# Project2.net
KiCad netlist of a schematic drawn in Altium Designer
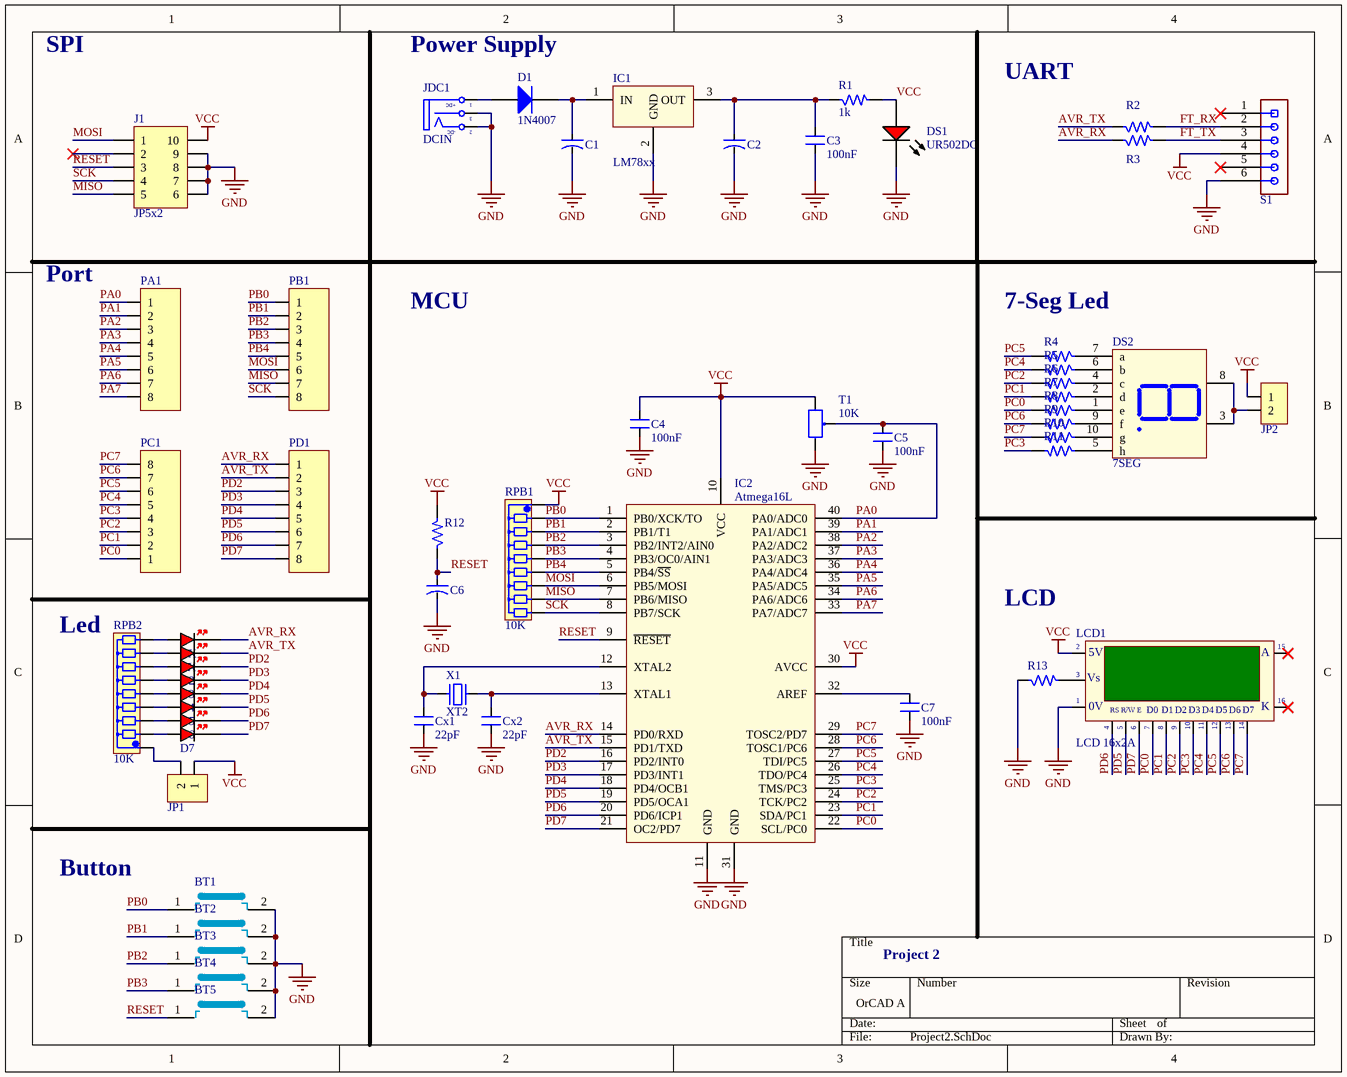
[diagram p0: Project2.SchDoc]

(export (version "E")
  (design (tool "Eeschema 10.0.6"))
  (components
    (comp (ref "BT1") (value "BT") (footprint "SW4") (libsource (lib "My library altium") (part "BUTTON")))
    (comp (ref "BT2") (value "BT") (footprint "SW4") (libsource (lib "My library altium") (part "BUTTON")))
    (comp (ref "BT3") (value "BT") (footprint "SW4") (libsource (lib "My library altium") (part "BUTTON")))
    (comp (ref "BT4") (value "BT") (footprint "SW4") (libsource (lib "My library altium") (part "BUTTON")))
    (comp (ref "BT5") (value "BT") (footprint "SW4") (libsource (lib "My library altium") (part "BUTTON")))
    (comp (ref "C1")
      (value "CN-ALU-DIP")
      (footprint "CA-ALU-8")
      (description "Capacitor (Semiconductor SIM Model)")
      (fields (field (name "PUBLISHER") "Altium Limited"))
      (libsource (lib "Altium Library") (part "CN-ALU-DIP"))
    )
    (comp (ref "C2")
      (value "CN-ALU-DIP")
      (footprint "CA-ALU-8")
      (description "Capacitor (Semiconductor SIM Model)")
      (fields (field (name "PUBLISHER") "Altium Limited"))
      (libsource (lib "Altium Library") (part "CN-ALU-DIP"))
    )
    (comp (ref "C3")
      (value "100nF")
      (footprint "CN1.5")
      (description "Cap np Cremic  682pF => 104 pF")
      (fields (field (name "Comment") "CN1.5") (field (name "SOURCE") "syhaunguyen.SchLib"))
      (libsource (lib "Ha Noi University of Science and Technology") (part "CN1.5"))
    )
    (comp (ref "C4")
      (value "100nF")
      (footprint "CN1.5")
      (description "Cap np Cremic  682pF => 104 pF")
      (fields (field (name "Comment") "CN1.5") (field (name "SOURCE") "syhaunguyen.SchLib"))
      (libsource (lib "Ha Noi University of Science and Technology") (part "CN1.5"))
    )
    (comp (ref "C5")
      (value "100nF")
      (footprint "CN1.5")
      (description "Cap np Cremic  682pF => 104 pF")
      (fields (field (name "Comment") "CN1.5") (field (name "SOURCE") "syhaunguyen.SchLib"))
      (libsource (lib "Ha Noi University of Science and Technology") (part "CN1.5"))
    )
    (comp (ref "C6")
      (value "CN-ALU-DIP")
      (footprint "CA-ALU-5W")
      (description "Capacitor (Semiconductor SIM Model)")
      (fields (field (name "PUBLISHER") "Altium Limited"))
      (libsource (lib "Altium Library") (part "CN-ALU-DIP"))
    )
    (comp (ref "C7")
      (value "100nF")
      (footprint "CN1.5")
      (description "Cap np Cremic  682pF => 104 pF")
      (fields (field (name "Comment") "CN1.5") (field (name "SOURCE") "syhaunguyen.SchLib"))
      (libsource (lib "Ha Noi University of Science and Technology") (part "CN1.5"))
    )
    (comp (ref "Cx1")
      (value "22pF")
      (footprint "CN1")
      (description "Cap np Cremic value 1pF => 100pF")
      (fields (field (name "Comment") "CN0") (field (name "SOURCE") "syhaunguyen.SchLib"))
      (libsource (lib "Ha Noi University of Science and Technology") (part "CN0"))
    )
    (comp (ref "Cx2")
      (value "22pF")
      (footprint "CN1")
      (description "Cap np Cremic value 1pF => 100pF")
      (fields (field (name "Comment") "CN0") (field (name "SOURCE") "syhaunguyen.SchLib"))
      (libsource (lib "Ha Noi University of Science and Technology") (part "CN0"))
    )
    (comp (ref "D1")
      (value "1N4007")
      (footprint "FAIR-DO-41-2")
      (description "General Purpose Rectifier, 1.1 V, 1.0 A, -55 to 175 degC, 2-Pin DO-41, RoHS, Tape and Reel")
      (fields (field (name "MANUFACTURER") "Fairchild"))
      (libsource (lib "Ha Noi University of Science and Technology") (part "KESE-D_K1A2-2"))
    )
    (comp (ref "D2")
      (value "Led Flat")
      (footprint "Led Flat")
      (description "Led Flat 2x5mm")
      (libsource (lib "LedFlat") (part "Led Flat"))
    )
    (comp (ref "D3")
      (value "Led Flat")
      (footprint "Led Flat")
      (description "Led Flat 2x5mm")
      (libsource (lib "LedFlat") (part "Led Flat"))
    )
    (comp (ref "D4")
      (value "Led Flat")
      (footprint "Led Flat")
      (description "Led Flat 2x5mm")
      (libsource (lib "LedFlat") (part "Led Flat"))
    )
    (comp (ref "D5")
      (value "Led Flat")
      (footprint "Led Flat")
      (description "Led Flat 2x5mm")
      (libsource (lib "LedFlat") (part "Led Flat"))
    )
    (comp (ref "D6")
      (value "Led Flat")
      (footprint "Led Flat")
      (description "Led Flat 2x5mm")
      (libsource (lib "LedFlat") (part "Led Flat"))
    )
    (comp (ref "D7")
      (value "Led Flat")
      (footprint "Led Flat")
      (description "Led Flat 2x5mm")
      (libsource (lib "LedFlat") (part "Led Flat"))
    )
    (comp (ref "DS1")
      (value "UR502DC")
      (footprint "CGX-UR502DC")
      (description "Red LED, 80 mW, 30 mA, -25 to 85 degC, 2-Pin THD")
      (fields (field (name "POWER") "80mW") (field (name "MANUFACTURER") "Shenzhen CGX"))
      (libsource (lib "Ha Noi University of Science and Technology") (part "LED-RED-AK-2"))
    )
    (comp (ref "DS2")
      (value "7SEG")
      (footprint "LED7SEG-1-0.56")
      (description "14.2 mm General Purpose Blue 7-Segment Display: CC, RH DP, Gray Surface")
      (fields (field (name "PUBLISHER") "Altium Limited"))
      (libsource (lib "Altium Library") (part "LED7SEG-1"))
    )
    (comp (ref "IC1")
      (value "LM78xx")
      (footprint "QTO-220H3")
      (description "Low-Power Dual Operational Amplifier")
      (fields (field (name "SOURCE") "syhaunguyen.SchLib"))
      (libsource (lib "Ha Noi University of Science and Technology") (part "LM78xx"))
    )
    (comp (ref "IC2")
      (value "Atmega16L")
      (footprint "DIP40PIN")
      (description "8-Bit AVR Microcontroller with 16K Bytes of In-System Programmable Flash Memory")
      (fields (field (name "SOURCE") "syhaunguyen.SchLib"))
      (libsource (lib "Ha Noi University of Science and Technology") (part "Atmega16L"))
    )
    (comp (ref "J1")
      (value "JP5x2")
      (footprint "JP5-D2T")
      (description "WR-PHD 2.54 mm Dual Socket Header")
      (fields
        (field (name "MANUFACTURER") "Würth Elektronik eiSos GmbH")
        (field (name "PARTNO") "61301021821")
        (field (name "CREATED BY") "Karrer Zheng")
      )
      (libsource (lib "Altium Library") (part "JP5x2"))
    )
    (comp (ref "JDC1")
      (value "DCIN")
      (footprint "DC-IN")
      (description "Jac DC input")
      (fields (field (name "SOURCE") "syhaunguyen.SchLib"))
      (libsource (lib "Ha Noi University of Science and Technology") (part "DCIN"))
    )
    (comp (ref "JP1")
      (value "JP1")
      (footprint "JP2-CLOSED")
      (description "WR-PHD 2.54 mm Angled Socket Header")
      (fields
        (field (name "MANUFACTURER") "Würth Elektronik eiSos GmbH")
        (field (name "PARTNO") "613002143121")
        (field (name "CREATED BY") "Karrer Zheng")
      )
      (libsource (lib "Altium Library") (part "JP2"))
    )
    (comp (ref "JP2")
      (value "JP2")
      (footprint "JP2-CLOSED")
      (description "WR-PHD 2.54 mm Angled Socket Header")
      (fields
        (field (name "MANUFACTURER") "Würth Elektronik eiSos GmbH")
        (field (name "PARTNO") "613002143121")
        (field (name "CREATED BY") "Karrer Zheng")
      )
      (libsource (lib "") (part "JP2_1"))
    )
    (comp (ref "LCD1")
      (value "LCD 16x2A")
      (footprint "LCD16X2N")
      (description "LCD dipslay 16 char, 2 line")
      (libsource (lib "Altium Library") (part "LCD16x2A"))
    )
    (comp (ref "PA1")
      (value "JP 1x8 2.54")
      (footprint "JP 1x8 DT")
      (description "Cắm")
      (libsource (lib "Altium_Lib_by_KhueNguyenCreator") (part "JP 1x8 2.54 Duc Thang"))
    )
    (comp (ref "PB1")
      (value "JP 1x8 2.54")
      (footprint "JP 1x8 DT")
      (description "Cắm")
      (libsource (lib "Altium_Lib_by_KhueNguyenCreator") (part "JP 1x8 2.54 Duc Thang"))
    )
    (comp (ref "PC1")
      (value "JP 1x8 2.54")
      (footprint "JP 1x8 DT")
      (description "Cắm")
      (libsource (lib "") (part "JP 1x8 2.54 Duc Thang_1"))
    )
    (comp (ref "PD1")
      (value "JP 1x8 2.54")
      (footprint "JP 1x8 DT")
      (description "Cắm")
      (libsource (lib "Altium_Lib_by_KhueNguyenCreator") (part "JP 1x8 2.54 Duc Thang"))
    )
    (comp (ref "R1")
      (value "1k")
      (footprint "R1/4W")
      (description "Resistor 1/4W")
      (libsource (lib "Library AL") (part "R"))
    )
    (comp (ref "R2")
      (value "R")
      (footprint "R1/4W")
      (description "Resistor 1/4W")
      (fields (field (name "SOURCE") "heromap.SchLib"))
      (libsource (lib "Ha Noi University of Science and Technology") (part "R"))
    )
    (comp (ref "R3")
      (value "R")
      (footprint "R1/4W")
      (description "Resistor 1/4W")
      (fields (field (name "SOURCE") "heromap.SchLib"))
      (libsource (lib "Ha Noi University of Science and Technology") (part "R"))
    )
    (comp (ref "R4")
      (value "R")
      (footprint "R1/4W")
      (description "Resistor 1/4W")
      (fields (field (name "SOURCE") "heromap.SchLib"))
      (libsource (lib "Ha Noi University of Science and Technology") (part "R"))
    )
    (comp (ref "R5")
      (value "R")
      (footprint "R1/4W")
      (description "Resistor 1/4W")
      (fields (field (name "SOURCE") "heromap.SchLib"))
      (libsource (lib "Ha Noi University of Science and Technology") (part "R"))
    )
    (comp (ref "R6")
      (value "R")
      (footprint "R1/4W")
      (description "Resistor 1/4W")
      (fields (field (name "SOURCE") "heromap.SchLib"))
      (libsource (lib "Ha Noi University of Science and Technology") (part "R"))
    )
    (comp (ref "R7")
      (value "R")
      (footprint "R1/4W")
      (description "Resistor 1/4W")
      (fields (field (name "SOURCE") "heromap.SchLib"))
      (libsource (lib "Ha Noi University of Science and Technology") (part "R"))
    )
    (comp (ref "R8")
      (value "R")
      (footprint "R1/4W")
      (description "Resistor 1/4W")
      (fields (field (name "SOURCE") "heromap.SchLib"))
      (libsource (lib "Ha Noi University of Science and Technology") (part "R"))
    )
    (comp (ref "R9")
      (value "R")
      (footprint "R1/4W")
      (description "Resistor 1/4W")
      (fields (field (name "SOURCE") "heromap.SchLib"))
      (libsource (lib "Ha Noi University of Science and Technology") (part "R"))
    )
    (comp (ref "R10")
      (value "R")
      (footprint "R1/4W")
      (description "Resistor 1/4W")
      (fields (field (name "SOURCE") "heromap.SchLib"))
      (libsource (lib "Ha Noi University of Science and Technology") (part "R"))
    )
    (comp (ref "R11")
      (value "R")
      (footprint "R1/4W")
      (description "Resistor 1/4W")
      (fields (field (name "SOURCE") "heromap.SchLib"))
      (libsource (lib "Ha Noi University of Science and Technology") (part "R"))
    )
    (comp (ref "R12")
      (value "R")
      (footprint "R1/4W")
      (description "Resistor 1/4W")
      (fields (field (name "SOURCE") "heromap.SchLib"))
      (libsource (lib "Ha Noi University of Science and Technology") (part "R"))
    )
    (comp (ref "R13")
      (value "R")
      (footprint "R1/4W")
      (description "Resistor 1/4W")
      (fields (field (name "SOURCE") "heromap.SchLib"))
      (libsource (lib "Ha Noi University of Science and Technology") (part "R"))
    )
    (comp (ref "RPB1")
      (value "10K")
      (footprint "RN8")
      (description "Resistor 8 (Thanh)")
      (libsource (lib "Altium Library") (part "RN8"))
    )
    (comp (ref "RPB2")
      (value "10K")
      (footprint "RN8")
      (description "Resistor 8 (Thanh)")
      (libsource (lib "") (part "RN8_1"))
    )
    (comp (ref "RX")
      (value "Led Flat")
      (footprint "Led Flat")
      (description "Led Flat 2x5mm")
      (libsource (lib "LedFlat") (part "Led Flat"))
    )
    (comp (ref "S1")
      (value "Socket 6P1R")
      (footprint "Socket 6P1R Vertical")
      (description "Socket 6Pins x 1Rows")
      (libsource (lib "Socket 6P1R") (part "Socket 6P1R"))
    )
    (comp (ref "T1")
      (value "10K")
      (footprint "BIEN TRO VI CHINH NAM")
      (description "Cắm")
      (libsource (lib "Altium_Lib_by_KhueNguyenCreator") (part "Bien Tro Tinh Chinh 10K Nam"))
    )
    (comp (ref "TX")
      (value "Led Flat")
      (footprint "Led Flat")
      (description "Led Flat 2x5mm")
      (libsource (lib "LedFlat") (part "Led Flat"))
    )
    (comp (ref "X1")
      (value "XT2")
      (footprint "XT2")
      (description "18 PIN, W 300mil, Pin to pin 100mil")
      (fields (field (name "SOURCE") "heromap.SchLib"))
      (libsource (lib "Ha Noi University of Science and Technology") (part "XT455k"))
    )
  )
  (nets
    (net (code "1") (name "/AVR_RX") (class "Default")
      (node (ref "IC2") (pin "14") (pinfunction "PD0/RXD_14") (pintype "passive"))
      (node (ref "PD1") (pin "1") (pinfunction "1_1") (pintype "passive"))
      (node (ref "R3") (pin "1") (pinfunction "1_1") (pintype "passive"))
      (node (ref "RX") (pin "K") (pinfunction "K_K") (pintype "passive"))
    )
    (net (code "2") (name "/AVR_TX") (class "Default")
      (node (ref "IC2") (pin "15") (pinfunction "PD1/TXD_15") (pintype "passive"))
      (node (ref "PD1") (pin "2") (pinfunction "2_2") (pintype "passive"))
      (node (ref "R2") (pin "1") (pinfunction "1_1") (pintype "passive"))
      (node (ref "TX") (pin "K") (pinfunction "K_K") (pintype "passive"))
    )
    (net (code "3") (name "/FT_RX") (class "Default")
      (node (ref "R2") (pin "2") (pinfunction "2_2") (pintype "passive"))
      (node (ref "S1") (pin "2") (pinfunction "2_2") (pintype "passive"))
    )
    (net (code "4") (name "/FT_TX") (class "Default")
      (node (ref "R3") (pin "2") (pinfunction "2_2") (pintype "passive"))
      (node (ref "S1") (pin "3") (pinfunction "3_3") (pintype "passive"))
    )
    (net (code "5") (name "/MISO") (class "Default")
      (node (ref "IC2") (pin "7") (pinfunction "PB6/MISO_7") (pintype "passive"))
      (node (ref "J1") (pin "5") (pinfunction "5_5") (pintype "passive"))
      (node (ref "PB1") (pin "7") (pinfunction "7_7") (pintype "passive"))
      (node (ref "RPB1") (pin "8") (pinfunction "8_8") (pintype "passive"))
    )
    (net (code "6") (name "/MOSI") (class "Default")
      (node (ref "IC2") (pin "6") (pinfunction "PB5/MOSI_6") (pintype "passive"))
      (node (ref "J1") (pin "1") (pinfunction "1_1") (pintype "passive"))
      (node (ref "PB1") (pin "6") (pinfunction "6_6") (pintype "passive"))
      (node (ref "RPB1") (pin "7") (pinfunction "7_7") (pintype "passive"))
    )
    (net (code "7") (name "/PA0") (class "Default")
      (node (ref "C5") (pin "2") (pinfunction "2_2") (pintype "passive"))
      (node (ref "IC2") (pin "40") (pinfunction "PA0/ADC0_40") (pintype "passive"))
      (node (ref "PA1") (pin "1") (pinfunction "1_1") (pintype "passive"))
      (node (ref "T1") (pin "2") (pinfunction "2_2") (pintype "passive"))
    )
    (net (code "8") (name "/PA1") (class "Default")
      (node (ref "IC2") (pin "39") (pinfunction "PA1/ADC1_39") (pintype "passive"))
      (node (ref "PA1") (pin "2") (pinfunction "2_2") (pintype "passive"))
    )
    (net (code "9") (name "/PA2") (class "Default")
      (node (ref "IC2") (pin "38") (pinfunction "PA2/ADC2_38") (pintype "passive"))
      (node (ref "PA1") (pin "3") (pinfunction "3_3") (pintype "passive"))
    )
    (net (code "10") (name "/PA3") (class "Default")
      (node (ref "IC2") (pin "37") (pinfunction "PA3/ADC3_37") (pintype "passive"))
      (node (ref "PA1") (pin "4") (pinfunction "4_4") (pintype "passive"))
    )
    (net (code "11") (name "/PA4") (class "Default")
      (node (ref "IC2") (pin "36") (pinfunction "PA4/ADC4_36") (pintype "passive"))
      (node (ref "PA1") (pin "5") (pinfunction "5_5") (pintype "passive"))
    )
    (net (code "12") (name "/PA5") (class "Default")
      (node (ref "IC2") (pin "35") (pinfunction "PA5/ADC5_35") (pintype "passive"))
      (node (ref "PA1") (pin "6") (pinfunction "6_6") (pintype "passive"))
    )
    (net (code "13") (name "/PA6") (class "Default")
      (node (ref "IC2") (pin "34") (pinfunction "PA6/ADC6_34") (pintype "passive"))
      (node (ref "PA1") (pin "7") (pinfunction "7_7") (pintype "passive"))
    )
    (net (code "14") (name "/PA7") (class "Default")
      (node (ref "IC2") (pin "33") (pinfunction "PA7/ADC7_33") (pintype "passive"))
      (node (ref "PA1") (pin "8") (pinfunction "8_8") (pintype "passive"))
    )
    (net (code "15") (name "/PB0") (class "Default")
      (node (ref "BT1") (pin "1") (pinfunction "1_1") (pintype "passive"))
      (node (ref "IC2") (pin "1") (pinfunction "PB0/XCK/TO_1") (pintype "passive"))
      (node (ref "PB1") (pin "1") (pinfunction "1_1") (pintype "passive"))
      (node (ref "RPB1") (pin "2") (pinfunction "2_2") (pintype "passive"))
    )
    (net (code "16") (name "/PB1") (class "Default")
      (node (ref "BT2") (pin "1") (pinfunction "1_1") (pintype "passive"))
      (node (ref "IC2") (pin "2") (pinfunction "PB1/T1_2") (pintype "passive"))
      (node (ref "PB1") (pin "2") (pinfunction "2_2") (pintype "passive"))
      (node (ref "RPB1") (pin "3") (pinfunction "3_3") (pintype "passive"))
    )
    (net (code "17") (name "/PB2") (class "Default")
      (node (ref "BT3") (pin "1") (pinfunction "1_1") (pintype "passive"))
      (node (ref "IC2") (pin "3") (pinfunction "PB2/INT2/AIN0_3") (pintype "passive"))
      (node (ref "PB1") (pin "3") (pinfunction "3_3") (pintype "passive"))
      (node (ref "RPB1") (pin "4") (pinfunction "4_4") (pintype "passive"))
    )
    (net (code "18") (name "/PB3") (class "Default")
      (node (ref "BT4") (pin "1") (pinfunction "1_1") (pintype "passive"))
      (node (ref "IC2") (pin "4") (pinfunction "PB3/OC0/AIN1_4") (pintype "passive"))
      (node (ref "PB1") (pin "4") (pinfunction "4_4") (pintype "passive"))
      (node (ref "RPB1") (pin "5") (pinfunction "5_5") (pintype "passive"))
    )
    (net (code "19") (name "/PB4") (class "Default")
      (node (ref "IC2") (pin "5") (pinfunction "PB4/~{SS}_5") (pintype "passive"))
      (node (ref "PB1") (pin "5") (pinfunction "5_5") (pintype "passive"))
      (node (ref "RPB1") (pin "6") (pinfunction "6_6") (pintype "passive"))
    )
    (net (code "20") (name "/PC0") (class "Default")
      (node (ref "IC2") (pin "22") (pinfunction "SCL/PC0_22") (pintype "passive"))
      (node (ref "LCD1") (pin "7") (pinfunction "D0_7") (pintype "passive"))
      (node (ref "PC1") (pin "1") (pinfunction "1_1") (pintype "passive"))
      (node (ref "R8") (pin "2") (pinfunction "2_2") (pintype "passive"))
    )
    (net (code "21") (name "/PC1") (class "Default")
      (node (ref "IC2") (pin "23") (pinfunction "SDA/PC1_23") (pintype "passive"))
      (node (ref "LCD1") (pin "8") (pinfunction "D1_8") (pintype "passive"))
      (node (ref "PC1") (pin "2") (pinfunction "2_2") (pintype "passive"))
      (node (ref "R7") (pin "2") (pinfunction "2_2") (pintype "passive"))
    )
    (net (code "22") (name "/PC2") (class "Default")
      (node (ref "IC2") (pin "24") (pinfunction "TCK/PC2_24") (pintype "passive"))
      (node (ref "LCD1") (pin "9") (pinfunction "D2_9") (pintype "passive"))
      (node (ref "PC1") (pin "3") (pinfunction "3_3") (pintype "passive"))
      (node (ref "R6") (pin "2") (pinfunction "2_2") (pintype "passive"))
    )
    (net (code "23") (name "/PC3") (class "Default")
      (node (ref "IC2") (pin "25") (pinfunction "TMS/PC3_25") (pintype "passive"))
      (node (ref "LCD1") (pin "10") (pinfunction "D3_10") (pintype "passive"))
      (node (ref "PC1") (pin "4") (pinfunction "4_4") (pintype "passive"))
      (node (ref "R11") (pin "2") (pinfunction "2_2") (pintype "passive"))
    )
    (net (code "24") (name "/PC4") (class "Default")
      (node (ref "IC2") (pin "26") (pinfunction "TDO/PC4_26") (pintype "passive"))
      (node (ref "LCD1") (pin "11") (pinfunction "D4_11") (pintype "passive"))
      (node (ref "PC1") (pin "5") (pinfunction "5_5") (pintype "passive"))
      (node (ref "R5") (pin "2") (pinfunction "2_2") (pintype "passive"))
    )
    (net (code "25") (name "/PC5") (class "Default")
      (node (ref "IC2") (pin "27") (pinfunction "TDI/PC5_27") (pintype "passive"))
      (node (ref "LCD1") (pin "12") (pinfunction "D5_12") (pintype "passive"))
      (node (ref "PC1") (pin "6") (pinfunction "6_6") (pintype "passive"))
      (node (ref "R4") (pin "2") (pinfunction "2_2") (pintype "passive"))
    )
    (net (code "26") (name "/PC6") (class "Default")
      (node (ref "IC2") (pin "28") (pinfunction "TOSC1/PC6_28") (pintype "passive"))
      (node (ref "LCD1") (pin "13") (pinfunction "D6_13") (pintype "passive"))
      (node (ref "PC1") (pin "7") (pinfunction "7_7") (pintype "passive"))
      (node (ref "R9") (pin "2") (pinfunction "2_2") (pintype "passive"))
    )
    (net (code "27") (name "/PC7") (class "Default")
      (node (ref "IC2") (pin "29") (pinfunction "TOSC2/PD7_29") (pintype "passive"))
      (node (ref "LCD1") (pin "14") (pinfunction "D7_14") (pintype "passive"))
      (node (ref "PC1") (pin "8") (pinfunction "8_8") (pintype "passive"))
      (node (ref "R10") (pin "2") (pinfunction "2_2") (pintype "passive"))
    )
    (net (code "28") (name "/PD2") (class "Default")
      (node (ref "D2") (pin "K") (pinfunction "K_K") (pintype "passive"))
      (node (ref "IC2") (pin "16") (pinfunction "PD2/INT0_16") (pintype "passive"))
      (node (ref "PD1") (pin "3") (pinfunction "3_3") (pintype "passive"))
    )
    (net (code "29") (name "/PD3") (class "Default")
      (node (ref "D3") (pin "K") (pinfunction "K_K") (pintype "passive"))
      (node (ref "IC2") (pin "17") (pinfunction "PD3/INT1_17") (pintype "passive"))
      (node (ref "PD1") (pin "4") (pinfunction "4_4") (pintype "passive"))
    )
    (net (code "30") (name "/PD4") (class "Default")
      (node (ref "D4") (pin "K") (pinfunction "K_K") (pintype "passive"))
      (node (ref "IC2") (pin "18") (pinfunction "PD4/OCB1_18") (pintype "passive"))
      (node (ref "PD1") (pin "5") (pinfunction "5_5") (pintype "passive"))
    )
    (net (code "31") (name "/PD5") (class "Default")
      (node (ref "D5") (pin "K") (pinfunction "K_K") (pintype "passive"))
      (node (ref "IC2") (pin "19") (pinfunction "PD5/OCA1_19") (pintype "passive"))
      (node (ref "LCD1") (pin "5") (pinfunction "R/~{W}_5") (pintype "passive"))
      (node (ref "PD1") (pin "6") (pinfunction "6_6") (pintype "passive"))
    )
    (net (code "32") (name "/PD6") (class "Default")
      (node (ref "D6") (pin "K") (pinfunction "K_K") (pintype "passive"))
      (node (ref "IC2") (pin "20") (pinfunction "PD6/ICP1_20") (pintype "passive"))
      (node (ref "LCD1") (pin "4") (pinfunction "RS_4") (pintype "passive"))
      (node (ref "PD1") (pin "7") (pinfunction "7_7") (pintype "passive"))
    )
    (net (code "33") (name "/PD7") (class "Default")
      (node (ref "D7") (pin "K") (pinfunction "K_K") (pintype "passive"))
      (node (ref "IC2") (pin "21") (pinfunction "OC2/PD7_21") (pintype "passive"))
      (node (ref "LCD1") (pin "6") (pinfunction "~{EN}_6") (pintype "passive"))
      (node (ref "PD1") (pin "8") (pinfunction "8_8") (pintype "passive"))
    )
    (net (code "34") (name "/RESET") (class "Default")
      (node (ref "BT5") (pin "1") (pinfunction "1_1") (pintype "passive"))
      (node (ref "C6") (pin "1") (pinfunction "1_1") (pintype "passive"))
      (node (ref "IC2") (pin "9") (pinfunction "~{RESET}_9") (pintype "passive"))
      (node (ref "J1") (pin "3") (pinfunction "3_3") (pintype "passive"))
      (node (ref "R12") (pin "1") (pinfunction "1_1") (pintype "passive"))
    )
    (net (code "35") (name "/SCK") (class "Default")
      (node (ref "IC2") (pin "8") (pinfunction "PB7/SCK_8") (pintype "passive"))
      (node (ref "J1") (pin "4") (pinfunction "4_4") (pintype "passive"))
      (node (ref "PB1") (pin "8") (pinfunction "8_8") (pintype "passive"))
      (node (ref "RPB1") (pin "9") (pinfunction "9_9") (pintype "passive"))
    )
    (net (code "36") (name "GND") (class "Default")
      (node (ref "BT1") (pin "2") (pinfunction "2_2") (pintype "passive"))
      (node (ref "BT2") (pin "2") (pinfunction "2_2") (pintype "passive"))
      (node (ref "BT3") (pin "2") (pinfunction "2_2") (pintype "passive"))
      (node (ref "BT4") (pin "2") (pinfunction "2_2") (pintype "passive"))
      (node (ref "BT5") (pin "2") (pinfunction "2_2") (pintype "passive"))
      (node (ref "C1") (pin "2") (pinfunction "2_2") (pintype "passive"))
      (node (ref "C2") (pin "2") (pinfunction "2_2") (pintype "passive"))
      (node (ref "C3") (pin "1") (pinfunction "1_1") (pintype "passive"))
      (node (ref "C4") (pin "1") (pinfunction "1_1") (pintype "passive"))
      (node (ref "C5") (pin "1") (pinfunction "1_1") (pintype "passive"))
      (node (ref "C6") (pin "2") (pinfunction "2_2") (pintype "passive"))
      (node (ref "C7") (pin "1") (pinfunction "1_1") (pintype "passive"))
      (node (ref "Cx1") (pin "1") (pinfunction "1_1") (pintype "passive"))
      (node (ref "Cx2") (pin "1") (pinfunction "1_1") (pintype "passive"))
      (node (ref "DS1") (pin "2") (pinfunction "K_2") (pintype "passive"))
      (node (ref "IC1") (pin "2") (pinfunction "GND_2") (pintype "passive"))
      (node (ref "IC2") (pin "11") (pinfunction "GND_11") (pintype "passive"))
      (node (ref "IC2") (pin "31") (pinfunction "GND_31") (pintype "passive"))
      (node (ref "J1") (pin "6") (pinfunction "6_6") (pintype "passive"))
      (node (ref "J1") (pin "7") (pinfunction "7_7") (pintype "passive"))
      (node (ref "J1") (pin "8") (pinfunction "8_8") (pintype "passive"))
      (node (ref "J1") (pin "9") (pinfunction "9_9") (pintype "passive"))
      (node (ref "JDC1") (pin "2") (pinfunction "TN_2") (pintype "passive"))
      (node (ref "JDC1") (pin "3") (pinfunction "S_3") (pintype "power_in"))
      (node (ref "LCD1") (pin "1") (pinfunction "GND_1") (pintype "passive"))
      (node (ref "R13") (pin "1") (pinfunction "1_1") (pintype "passive"))
      (node (ref "S1") (pin "6") (pinfunction "6_6") (pintype "passive"))
      (node (ref "T1") (pin "3") (pinfunction "3_3") (pintype "passive"))
    )
    (net (code "37") (name "Net-(D1-A)") (class "Default")
      (node (ref "D1") (pin "2") (pinfunction "A_2") (pintype "passive"))
      (node (ref "JDC1") (pin "1") (pinfunction "T_1") (pintype "passive"))
    )
    (net (code "38") (name "Net-(D1-K)") (class "Default")
      (node (ref "C1") (pin "1") (pinfunction "1_1") (pintype "passive"))
      (node (ref "D1") (pin "1") (pinfunction "K_1") (pintype "passive"))
      (node (ref "IC1") (pin "1") (pinfunction "IN_1") (pintype "passive"))
    )
    (net (code "39") (name "Net-(D2-PadA)") (class "Default")
      (node (ref "D2") (pin "A") (pinfunction "A_A") (pintype "passive"))
      (node (ref "RPB2") (pin "7") (pinfunction "7_7") (pintype "passive"))
    )
    (net (code "40") (name "Net-(D3-PadA)") (class "Default")
      (node (ref "D3") (pin "A") (pinfunction "A_A") (pintype "passive"))
      (node (ref "RPB2") (pin "6") (pinfunction "6_6") (pintype "passive"))
    )
    (net (code "41") (name "Net-(D4-PadA)") (class "Default")
      (node (ref "D4") (pin "A") (pinfunction "A_A") (pintype "passive"))
      (node (ref "RPB2") (pin "5") (pinfunction "5_5") (pintype "passive"))
    )
    (net (code "42") (name "Net-(D5-PadA)") (class "Default")
      (node (ref "D5") (pin "A") (pinfunction "A_A") (pintype "passive"))
      (node (ref "RPB2") (pin "4") (pinfunction "4_4") (pintype "passive"))
    )
    (net (code "43") (name "Net-(D6-PadA)") (class "Default")
      (node (ref "D6") (pin "A") (pinfunction "A_A") (pintype "passive"))
      (node (ref "RPB2") (pin "3") (pinfunction "3_3") (pintype "passive"))
    )
    (net (code "44") (name "Net-(D7-PadA)") (class "Default")
      (node (ref "D7") (pin "A") (pinfunction "A_A") (pintype "passive"))
      (node (ref "RPB2") (pin "2") (pinfunction "2_2") (pintype "passive"))
    )
    (net (code "45") (name "Net-(DS2-Vcc-Pad3)") (class "Default")
      (node (ref "DS2") (pin "3") (pinfunction "Vcc_3") (pintype "passive"))
      (node (ref "DS2") (pin "8") (pinfunction "Vcc_8") (pintype "passive"))
      (node (ref "JP2") (pin "2") (pinfunction "2_2") (pintype "passive"))
    )
    (net (code "46") (name "Net-(DS2-a)") (class "Default")
      (node (ref "DS2") (pin "7") (pinfunction "a_7") (pintype "passive"))
      (node (ref "R4") (pin "1") (pinfunction "1_1") (pintype "passive"))
    )
    (net (code "47") (name "Net-(DS2-b)") (class "Default")
      (node (ref "DS2") (pin "6") (pinfunction "b_6") (pintype "passive"))
      (node (ref "R5") (pin "1") (pinfunction "1_1") (pintype "passive"))
    )
    (net (code "48") (name "Net-(DS2-c)") (class "Default")
      (node (ref "DS2") (pin "4") (pinfunction "c_4") (pintype "passive"))
      (node (ref "R6") (pin "1") (pinfunction "1_1") (pintype "passive"))
    )
    (net (code "49") (name "Net-(DS2-d)") (class "Default")
      (node (ref "DS2") (pin "2") (pinfunction "d_2") (pintype "passive"))
      (node (ref "R7") (pin "1") (pinfunction "1_1") (pintype "passive"))
    )
    (net (code "50") (name "Net-(DS2-e)") (class "Default")
      (node (ref "DS2") (pin "1") (pinfunction "e_1") (pintype "passive"))
      (node (ref "R8") (pin "1") (pinfunction "1_1") (pintype "passive"))
    )
    (net (code "51") (name "Net-(DS2-f)") (class "Default")
      (node (ref "DS2") (pin "9") (pinfunction "f_9") (pintype "passive"))
      (node (ref "R9") (pin "1") (pinfunction "1_1") (pintype "passive"))
    )
    (net (code "52") (name "Net-(DS2-g)") (class "Default")
      (node (ref "DS2") (pin "10") (pinfunction "g_10") (pintype "passive"))
      (node (ref "R10") (pin "1") (pinfunction "1_1") (pintype "passive"))
    )
    (net (code "53") (name "Net-(DS2-h)") (class "Default")
      (node (ref "DS2") (pin "5") (pinfunction "h_5") (pintype "passive"))
      (node (ref "R11") (pin "1") (pinfunction "1_1") (pintype "passive"))
    )
    (net (code "54") (name "Net-(IC1-OUT)") (class "Default")
      (node (ref "C2") (pin "1") (pinfunction "1_1") (pintype "passive"))
      (node (ref "C3") (pin "2") (pinfunction "2_2") (pintype "passive"))
      (node (ref "IC1") (pin "3") (pinfunction "OUT_3") (pintype "passive"))
      (node (ref "R1") (pin "1") (pinfunction "1_1") (pintype "passive"))
    )
    (net (code "55") (name "Net-(IC2-AREF)") (class "Default")
      (node (ref "C7") (pin "2") (pinfunction "2_2") (pintype "passive"))
      (node (ref "IC2") (pin "32") (pinfunction "AREF_32") (pintype "passive"))
    )
    (net (code "56") (name "Net-(IC2-XTAL1)") (class "Default")
      (node (ref "Cx2") (pin "2") (pinfunction "2_2") (pintype "passive"))
      (node (ref "IC2") (pin "13") (pinfunction "XTAL1_13") (pintype "passive"))
      (node (ref "X1") (pin "2") (pinfunction "2_2") (pintype "passive"))
    )
    (net (code "57") (name "Net-(IC2-XTAL2)") (class "Default")
      (node (ref "Cx1") (pin "2") (pinfunction "2_2") (pintype "passive"))
      (node (ref "IC2") (pin "12") (pinfunction "XTAL2_12") (pintype "passive"))
      (node (ref "X1") (pin "1") (pinfunction "1_1") (pintype "passive"))
    )
    (net (code "58") (name "Net-(JP1-Pad2)") (class "Default")
      (node (ref "JP1") (pin "2") (pinfunction "2_2") (pintype "passive"))
      (node (ref "RPB2") (pin "1") (pinfunction "1_1") (pintype "passive"))
    )
    (net (code "59") (name "Net-(LCD1-VEE)") (class "Default")
      (node (ref "LCD1") (pin "3") (pinfunction "VEE_3") (pintype "passive"))
      (node (ref "R13") (pin "2") (pinfunction "2_2") (pintype "passive"))
    )
    (net (code "60") (name "Net-(RPB2-Pad8)") (class "Default")
      (node (ref "RPB2") (pin "8") (pinfunction "8_8") (pintype "passive"))
      (node (ref "TX") (pin "A") (pinfunction "A_A") (pintype "passive"))
    )
    (net (code "61") (name "Net-(RPB2-Pad9)") (class "Default")
      (node (ref "RPB2") (pin "9") (pinfunction "9_9") (pintype "passive"))
      (node (ref "RX") (pin "A") (pinfunction "A_A") (pintype "passive"))
    )
    (net (code "62") (name "VCC") (class "Default")
      (node (ref "C4") (pin "2") (pinfunction "2_2") (pintype "passive"))
      (node (ref "DS1") (pin "1") (pinfunction "A_1") (pintype "passive"))
      (node (ref "IC2") (pin "10") (pinfunction "VCC_10") (pintype "passive"))
      (node (ref "IC2") (pin "30") (pinfunction "AVCC_30") (pintype "passive"))
      (node (ref "J1") (pin "10") (pinfunction "10_10") (pintype "passive"))
      (node (ref "JP1") (pin "1") (pinfunction "1_1") (pintype "passive"))
      (node (ref "JP2") (pin "1") (pinfunction "1_1") (pintype "passive"))
      (node (ref "LCD1") (pin "2") (pinfunction "VDD_2") (pintype "passive"))
      (node (ref "R1") (pin "2") (pinfunction "2_2") (pintype "passive"))
      (node (ref "R12") (pin "2") (pinfunction "2_2") (pintype "passive"))
      (node (ref "RPB1") (pin "1") (pinfunction "1_1") (pintype "passive"))
      (node (ref "S1") (pin "4") (pinfunction "4_4") (pintype "passive"))
      (node (ref "T1") (pin "1") (pinfunction "1_1") (pintype "passive"))
    )
    (net (code "63") (name "unconnected-(J1-Pad2)") (class "Default")
      (node (ref "J1") (pin "2") (pinfunction "2_2") (pintype "passive+no_connect"))
    )
    (net (code "64") (name "unconnected-(LCD1-A-Pad15)") (class "Default")
      (node (ref "LCD1") (pin "15") (pinfunction "A_15") (pintype "passive+no_connect"))
    )
    (net (code "65") (name "unconnected-(LCD1-K-Pad16)") (class "Default")
      (node (ref "LCD1") (pin "16") (pinfunction "K_16") (pintype "passive+no_connect"))
    )
    (net (code "66") (name "unconnected-(S1-Pad1)") (class "Default")
      (node (ref "S1") (pin "1") (pinfunction "1_1") (pintype "passive+no_connect"))
    )
    (net (code "67") (name "unconnected-(S1-Pad5)") (class "Default")
      (node (ref "S1") (pin "5") (pinfunction "5_5") (pintype "passive+no_connect"))
    )
  )
)
